# Mini-DSO.net
KiCad netlist of a schematic drawn in Altium Designer
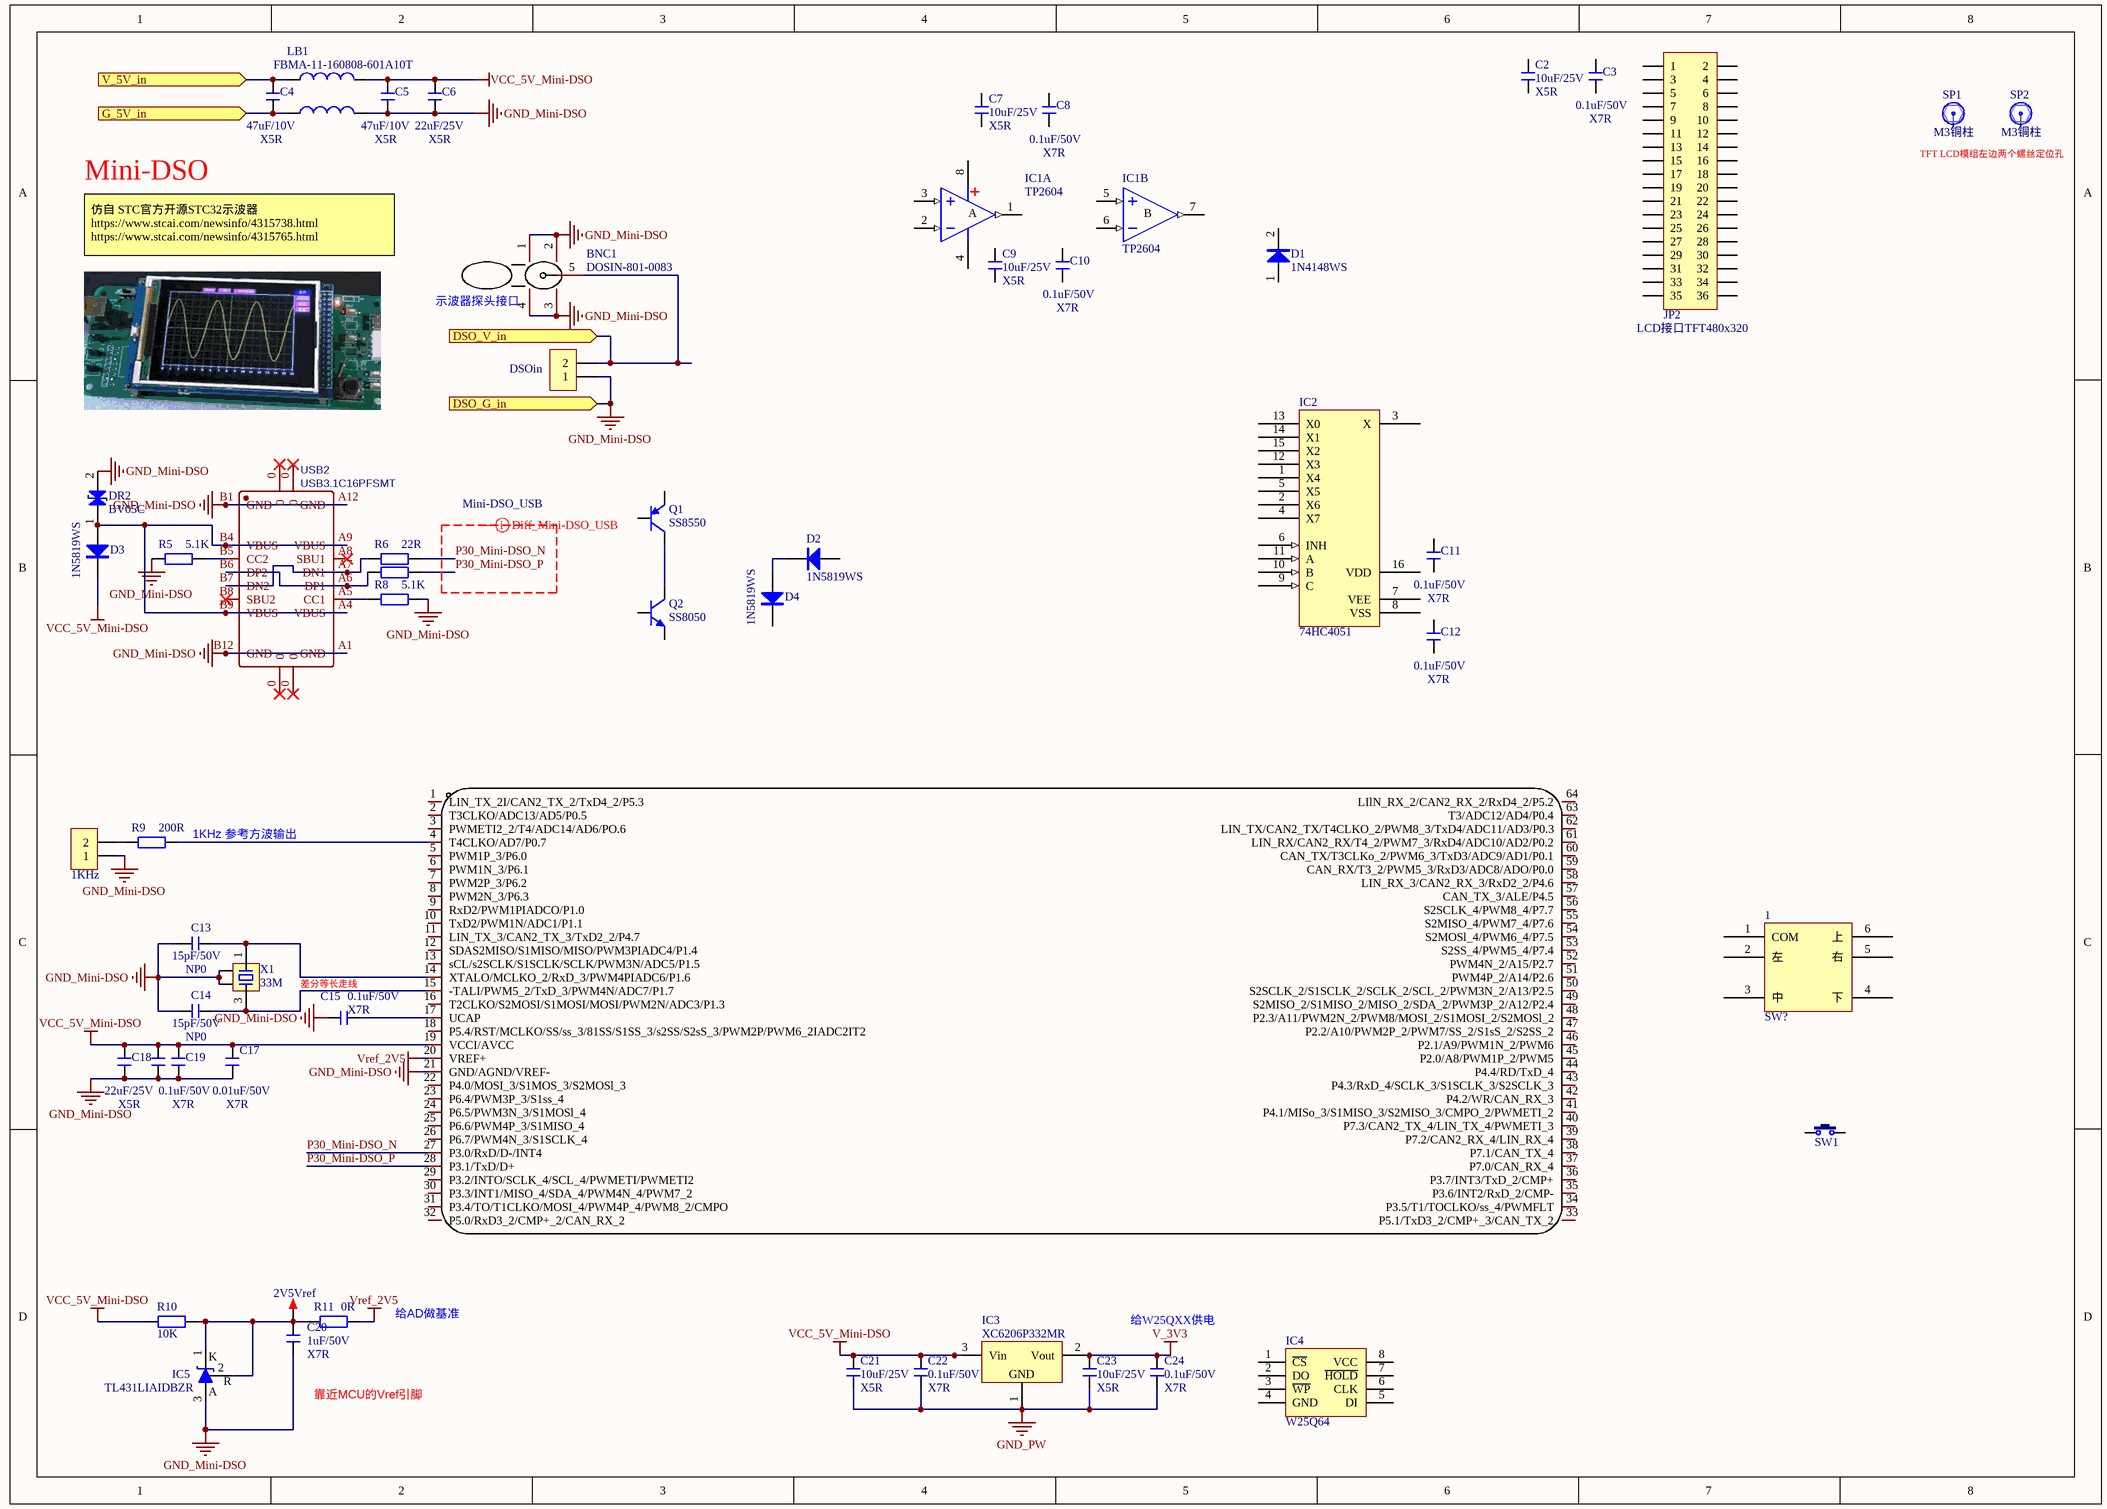
[diagram p0: Mini-DSO.SchDoc]

(export (version "E")
  (design (tool "Eeschema 10.0.6"))
  (components
    (comp (ref "1")
      (value "SW?")
      (footprint "TSW 10x10x9-5Key-LS")
      (description "五向按键")
      (libsource (lib "IC_temp") (part "5Key"))
    )
    (comp (ref "BNC1")
      (value "DOSIN-801-0083")
      (footprint "BNC-TH_DOSIN-801-0083")
      (description "示波器探头插座，DOSIN-801-0083")
      (libsource (lib "IC_temp") (part "BNC插座"))
    )
    (comp (ref "C2")
      (value "10uF/25V")
      (footprint "C 0603_L")
      (description "无极性贴片电容 X5R")
      (fields (field (name "BOM名称") "X5R"))
      (libsource (lib "Foundation_temp") (part "C X5R"))
    )
    (comp (ref "C3")
      (value "0.1uF/50V")
      (footprint "C 0402_L")
      (description "无极性贴片电容 X7R")
      (fields (field (name "BOM名称") "X7R"))
      (libsource (lib "Foundation_temp") (part "C X7R"))
    )
    (comp (ref "C4")
      (value "47uF/10V")
      (footprint "C 1206_L")
      (description "无极性贴片电容 X5R")
      (fields (field (name "BOM名称") "X5R"))
      (libsource (lib "Foundation_temp") (part "C X5R"))
    )
    (comp (ref "C5")
      (value "47uF/10V")
      (footprint "C 1206_L")
      (description "无极性贴片电容 X5R")
      (fields (field (name "BOM名称") "X5R"))
      (libsource (lib "Foundation_temp") (part "C X5R"))
    )
    (comp (ref "C6")
      (value "22uF/25V")
      (footprint "C 0805_L")
      (description "无极性贴片电容 X5R")
      (fields (field (name "BOM名称") "X5R"))
      (libsource (lib "Foundation_temp") (part "C X5R"))
    )
    (comp (ref "C7")
      (value "10uF/25V")
      (footprint "C 0603_L")
      (description "无极性贴片电容 X5R")
      (fields (field (name "BOM名称") "X5R"))
      (libsource (lib "Foundation_temp") (part "C X5R"))
    )
    (comp (ref "C8")
      (value "0.1uF/50V")
      (footprint "C 0402_L")
      (description "无极性贴片电容 X7R")
      (fields (field (name "BOM名称") "X7R"))
      (libsource (lib "Foundation_temp") (part "C X7R"))
    )
    (comp (ref "C9")
      (value "10uF/25V")
      (footprint "C 0603_L")
      (description "无极性贴片电容 X5R")
      (fields (field (name "BOM名称") "X5R"))
      (libsource (lib "Foundation_temp") (part "C X5R"))
    )
    (comp (ref "C10")
      (value "0.1uF/50V")
      (footprint "C 0402_L")
      (description "无极性贴片电容 X7R")
      (fields (field (name "BOM名称") "X7R"))
      (libsource (lib "Foundation_temp") (part "C X7R"))
    )
    (comp (ref "C11")
      (value "0.1uF/50V")
      (footprint "C 0402_L")
      (description "无极性贴片电容 X7R")
      (fields (field (name "BOM名称") "X7R"))
      (libsource (lib "Foundation_temp") (part "C X7R"))
    )
    (comp (ref "C12")
      (value "0.1uF/50V")
      (footprint "C 0402_L")
      (description "无极性贴片电容 X7R")
      (fields (field (name "BOM名称") "X7R"))
      (libsource (lib "Foundation_temp") (part "C X7R"))
    )
    (comp (ref "C13")
      (value "15pF/50V")
      (footprint "C 0402_L")
      (description "无极性贴片电容 NP0")
      (fields (field (name "BOM名称") "NP0"))
      (libsource (lib "Foundation_temp") (part "C NP0"))
    )
    (comp (ref "C14")
      (value "15pF/50V")
      (footprint "C 0402_L")
      (description "无极性贴片电容 NP0")
      (fields (field (name "BOM名称") "NP0"))
      (libsource (lib "Foundation_temp") (part "C NP0"))
    )
    (comp (ref "C15")
      (value "0.1uF/50V")
      (footprint "C 0402_L")
      (description "无极性贴片电容 X7R")
      (fields (field (name "BOM名称") "X7R"))
      (libsource (lib "Foundation_temp") (part "C X7R"))
    )
    (comp (ref "C16")
      (value "0.1uF/50V")
      (footprint "C 0402_L")
      (description "无极性贴片电容 X7R")
      (libsource (lib "Foundation_temp") (part "C X7R"))
    )
    (comp (ref "C17")
      (value "0.01uF/50V")
      (footprint "C 0402_L")
      (description "无极性贴片电容 X7R")
      (fields (field (name "BOM名称") "X7R"))
      (libsource (lib "Foundation_temp") (part "C X7R"))
    )
    (comp (ref "C18")
      (value "22uF/25V")
      (footprint "C 0805_L")
      (description "无极性贴片电容 X5R")
      (fields (field (name "BOM名称") "X5R"))
      (libsource (lib "Foundation_temp") (part "C X5R"))
    )
    (comp (ref "C19")
      (value "0.1uF/50V")
      (footprint "C 0402_L")
      (description "无极性贴片电容 X7R")
      (fields (field (name "BOM名称") "X7R"))
      (libsource (lib "Foundation_temp") (part "C X7R"))
    )
    (comp (ref "C20")
      (value "1uF/50V")
      (footprint "C 0603_L")
      (description "无极性贴片电容 X7R")
      (fields (field (name "BOM名称") "X7R"))
      (libsource (lib "Foundation_temp") (part "C X7R"))
    )
    (comp (ref "C21")
      (value "10uF/25V")
      (footprint "C 0603_L")
      (description "无极性贴片电容 X5R")
      (fields (field (name "BOM名称") "X5R"))
      (libsource (lib "Foundation_temp") (part "C X5R"))
    )
    (comp (ref "C22")
      (value "0.1uF/50V")
      (footprint "C 0402_L")
      (description "无极性贴片电容 X7R")
      (fields (field (name "BOM名称") "X7R"))
      (libsource (lib "Foundation_temp") (part "C X7R"))
    )
    (comp (ref "C23")
      (value "10uF/25V")
      (footprint "C 0603_L")
      (description "无极性贴片电容 X5R")
      (fields (field (name "BOM名称") "X5R"))
      (libsource (lib "Foundation_temp") (part "C X5R"))
    )
    (comp (ref "C24")
      (value "0.1uF/50V")
      (footprint "C 0402_L")
      (description "无极性贴片电容 X7R")
      (fields (field (name "BOM名称") "X7R"))
      (libsource (lib "Foundation_temp") (part "C X7R"))
    )
    (comp (ref "D1")
      (value "1N4148WS")
      (footprint "SOD-323")
      (description "高速开关二极管")
      (fields (field (name "版权归属") "源创客"))
      (libsource (lib "8.1   - 二极管-整流桥") (part "1N4148"))
    )
    (comp (ref "D2")
      (value "1N5819WS")
      (footprint "SOD-323")
      (description "肖特基二极管")
      (fields (field (name "版权归属") "源创客"))
      (libsource (lib "8.1   - 二极管-整流桥") (part "1N5819"))
    )
    (comp (ref "D3")
      (value "1N5819WS")
      (footprint "SOD-323")
      (description "肖特基二极管")
      (fields (field (name "版权归属") "源创客"))
      (libsource (lib "8.1   - 二极管-整流桥") (part "1N5819"))
    )
    (comp (ref "D4")
      (value "1N5819WS")
      (footprint "SOD-323")
      (description "肖特基二极管")
      (fields (field (name "版权归属") "源创客"))
      (libsource (lib "8.1   - 二极管-整流桥") (part "1N5819"))
    )
    (comp (ref "DR2")
      (value "BV05C")
      (footprint "SOD-323")
      (description "瞬态电压抑制二极管")
      (fields (field (name "版权归属") "源创客"))
      (libsource (lib "8.1   - 二极管-整流桥") (part "DR"))
    )
    (comp (ref "IC1")
      (value "TP2604")
      (footprint "SOP8_N")
      (description "双路运放")
      (fields (field (name "版权归属") "源创客"))
      (libsource (lib "1.5   - 运放-功放") (part "LM358"))
    )
    (comp (ref "IC2")
      (value "74HC4051")
      (footprint "SOP16_N")
      (description "八选一")
      (libsource (lib "IC_temp") (part "CD4051"))
    )
    (comp (ref "IC3")
      (value "XC6206P332MR")
      (footprint "SOT23-3N")
      (description "低压差线性稳压芯片")
      (fields (field (name "版权归属") "源创客"))
      (libsource (lib "1.3   - 电源类芯片") (part "XC6206P332MR"))
    )
    (comp (ref "IC4")
      (value "W25Q64")
      (footprint "SOP8W_N")
      (description "外置Flash")
      (fields (field (name "版权归属") "源创客"))
      (libsource (lib "1.1   - IC芯片") (part "W25Qxx"))
    )
    (comp (ref "IC5")
      (value "TL431LIAIDBZR")
      (footprint "SOT23-3N")
      (description "可调基准稳压芯片")
      (fields (field (name "版权归属") "源创客"))
      (libsource (lib "1.3   - 电源类芯片") (part "TL431_SMD"))
    )
    (comp (ref "JP1")
      (value "DSOin")
      (footprint "HDR2.54-WS-2P")
      (description "2P接插件")
      (fields (field (name "版权归属") "源创客"))
      (libsource (lib "4.6   - 接插件-脚距2.54") (part "Header 2"))
    )
    (comp (ref "JP2")
      (value "LCD接口TFT480x320")
      (footprint "HDR2.54-LI-2x18P")
      (description "18*2P接插件")
      (fields (field (name "版权归属") "源创客"))
      (libsource (lib "4.6   - 接插件-脚距2.54") (part "Header 18X2"))
    )
    (comp (ref "JP3")
      (value "1KHz")
      (footprint "HDR2.54-WS-2P")
      (description "2P接插件")
      (fields (field (name "版权归属") "源创客"))
      (libsource (lib "4.6   - 接插件-脚距2.54") (part "Header 2"))
    )
    (comp (ref "LB1")
      (value "FBMA-11-160808-601A10T")
      (footprint "FB 0603_L")
      (description "磁珠 600R@100MHz")
      (fields (field (name "版权归属") "源创客"))
      (libsource (lib "3.1   - 电阻-电容-电感") (part "LB"))
    )
    (comp (ref "LB2")
      (value "FBMA-11-160808-601A10T")
      (footprint "FB 0603_L")
      (description "磁珠 600R@100MHz")
      (fields (field (name "版权归属") "源创客"))
      (libsource (lib "3.1   - 电阻-电容-电感") (part "LB"))
    )
    (comp (ref "Q1")
      (value "SS8550")
      (footprint "SOT23-3N")
      (description "高频放大-PNP型")
      (fields (field (name "版权归属") "源创客"))
      (libsource (lib "6.2   - 三极管") (part "8550-SMD"))
    )
    (comp (ref "Q2")
      (value "SS8050")
      (footprint "SOT23-3N")
      (description "高频放大-NPN型")
      (fields (field (name "版权归属") "源创客"))
      (libsource (lib "6.2   - 三极管") (part "8050-SMD"))
    )
    (comp (ref "R5")
      (value "5.1K")
      (footprint "R 0402_L")
      (description "贴片电阻 E-96 1%")
      (libsource (lib "Foundation_temp") (part "R"))
    )
    (comp (ref "R6")
      (value "22R")
      (footprint "R 0402_L")
      (description "贴片电阻 E-96 1%")
      (libsource (lib "Foundation_temp") (part "R"))
    )
    (comp (ref "R7")
      (value "22R")
      (footprint "R 0402_L")
      (description "贴片电阻 E-96 1%")
      (libsource (lib "Foundation_temp") (part "R"))
    )
    (comp (ref "R8")
      (value "5.1K")
      (footprint "R 0402_L")
      (description "贴片电阻 E-96 1%")
      (libsource (lib "Foundation_temp") (part "R"))
    )
    (comp (ref "R9")
      (value "200R")
      (footprint "R 0402_L")
      (description "贴片电阻 E-96 1%")
      (libsource (lib "Foundation_temp") (part "R"))
    )
    (comp (ref "R10")
      (value "10K")
      (footprint "R 0402_L")
      (description "贴片电阻 E-96 1%")
      (libsource (lib "Foundation_temp") (part "R"))
    )
    (comp (ref "R11")
      (value "0R")
      (footprint "R 0402_L")
      (description "贴片电阻 E-96 1%")
      (libsource (lib "Foundation_temp") (part "R"))
    )
    (comp (ref "SP1")
      (value "M3铜柱")
      (footprint "M3x4_L")
      (description "铜柱")
      (fields (field (name "版权归属") "源创客"))
      (libsource (lib "15.1 - 未分类器件") (part "铜柱小焊盘"))
    )
    (comp (ref "SP2")
      (value "M3铜柱")
      (footprint "M3x4_L")
      (description "铜柱")
      (fields (field (name "版权归属") "源创客"))
      (libsource (lib "15.1 - 未分类器件") (part "铜柱小焊盘"))
    )
    (comp (ref "SW1")
      (value "3x6x5")
      (footprint "TSW SMD-3*6*2.5")
      (description "3x6轻触开关")
      (fields (field (name "版权归属") "源创客"))
      (libsource (lib "5.1   - 按键-开关") (part "TSW 3x6"))
    )
    (comp (ref "TP3")
      (value "2V5Vref")
      (footprint "TEST 1")
      (description "测试点")
      (fields (field (name "版权归属") "源创客"))
      (libsource (lib "15.1 - 未分类器件") (part "TEST"))
    )
    (comp (ref "U1")
      (value "STC32G12K128-Beta-LQFP64")
      (footprint "LQFP64 14x14_N")
      (fields (field (name "MANUFACTURER") "STC(宏晶)"))
      (libsource (lib "STC32G12K128-BETA-LQFP64") (part "STC32G12K128-Beta-LQFP64"))
    )
    (comp (ref "USB2")
      (value "USB3.1C16PFSMT")
      (footprint "TYPE-C-USB-17")
      (libsource (lib "type-c-sch") (part "USB3.1C16PFSMT"))
    )
    (comp (ref "X1")
      (value "33M")
      (footprint "OSC 3225-4P")
      (description "4脚无源晶振")
      (fields (field (name "版权归属") "源创客"))
      (libsource (lib "10.1 - 保险丝-晶振") (part "XTAL-4P"))
    )
  )
  (nets
    (net (code "1") (name "/DSO_V_in") (class "Default")
      (node (ref "BNC1") (pin "5") (pinfunction "5_5") (pintype "passive"))
      (node (ref "JP1") (pin "2") (pinfunction "2_2") (pintype "passive"))
    )
    (net (code "2") (name "/G_5V_in") (class "Default")
      (node (ref "C4") (pin "1") (pinfunction "1_1") (pintype "passive"))
      (node (ref "LB2") (pin "1") (pinfunction "1_1") (pintype "passive"))
    )
    (net (code "3") (name "/P30_Mini-DSO_N") (class "Default")
      (node (ref "R6") (pin "1") (pinfunction "1_1") (pintype "passive"))
      (node (ref "U1") (pin "27") (pinfunction "P3.0/RxD/D-/INT4_27") (pintype "passive"))
    )
    (net (code "4") (name "/P30_Mini-DSO_P") (class "Default")
      (node (ref "R7") (pin "1") (pinfunction "1_1") (pintype "passive"))
      (node (ref "U1") (pin "28") (pinfunction "P3.1/TxD/D+_28") (pintype "passive"))
    )
    (net (code "5") (name "/V_5V_in") (class "Default")
      (node (ref "C4") (pin "2") (pinfunction "2_2") (pintype "passive"))
      (node (ref "LB1") (pin "1") (pinfunction "1_1") (pintype "passive"))
    )
    (net (code "6") (name "GND_Mini-DSO") (class "Default")
      (node (ref "BNC1") (pin "1") (pinfunction "1_1") (pintype "passive"))
      (node (ref "BNC1") (pin "2") (pinfunction "2_2") (pintype "passive"))
      (node (ref "BNC1") (pin "3") (pinfunction "3_3") (pintype "passive"))
      (node (ref "BNC1") (pin "4") (pinfunction "4_4") (pintype "passive"))
      (node (ref "C13") (pin "2") (pinfunction "2_2") (pintype "passive"))
      (node (ref "C14") (pin "2") (pinfunction "2_2") (pintype "passive"))
      (node (ref "C15") (pin "2") (pinfunction "2_2") (pintype "passive"))
      (node (ref "C16") (pin "2") (pinfunction "2_2") (pintype "passive"))
      (node (ref "C17") (pin "2") (pinfunction "2_2") (pintype "passive"))
      (node (ref "C18") (pin "1") (pinfunction "1_1") (pintype "passive"))
      (node (ref "C19") (pin "2") (pinfunction "2_2") (pintype "passive"))
      (node (ref "C20") (pin "1") (pinfunction "1_1") (pintype "passive"))
      (node (ref "C5") (pin "1") (pinfunction "1_1") (pintype "passive"))
      (node (ref "C6") (pin "1") (pinfunction "1_1") (pintype "passive"))
      (node (ref "DR2") (pin "2") (pinfunction "K_2") (pintype "passive"))
      (node (ref "IC5") (pin "3") (pinfunction "A_3") (pintype "passive"))
      (node (ref "JP1") (pin "1") (pinfunction "1_1") (pintype "passive"))
      (node (ref "JP3") (pin "1") (pinfunction "1_1") (pintype "passive"))
      (node (ref "LB2") (pin "2") (pinfunction "2_2") (pintype "passive"))
      (node (ref "R5") (pin "2") (pinfunction "2_2") (pintype "passive"))
      (node (ref "R8") (pin "1") (pinfunction "1_1") (pintype "passive"))
      (node (ref "U1") (pin "21") (pinfunction "GND/AGND/VREF-_21") (pintype "passive"))
      (node (ref "USB2") (pin "A1") (pinfunction "GND_A1") (pintype "passive"))
      (node (ref "USB2") (pin "A12") (pinfunction "GND_A12") (pintype "passive"))
      (node (ref "USB2") (pin "B1") (pinfunction "GND_B1") (pintype "passive"))
      (node (ref "USB2") (pin "B12") (pinfunction "GND_B12") (pintype "passive"))
      (node (ref "X1") (pin "2") (pinfunction "2_2") (pintype "passive"))
      (node (ref "X1") (pin "4") (pinfunction "4_4") (pintype "passive"))
    )
    (net (code "7") (name "GND_PW") (class "Default")
      (node (ref "C21") (pin "1") (pinfunction "1_1") (pintype "passive"))
      (node (ref "C22") (pin "2") (pinfunction "2_2") (pintype "passive"))
      (node (ref "C23") (pin "1") (pinfunction "1_1") (pintype "passive"))
      (node (ref "C24") (pin "2") (pinfunction "2_2") (pintype "passive"))
      (node (ref "IC3") (pin "1") (pinfunction "GND_1") (pintype "passive"))
    )
    (net (code "8") (name "Net-(D2-K)") (class "Default")
      (node (ref "D2") (pin "2") (pinfunction "K_2") (pintype "passive"))
      (node (ref "D4") (pin "1") (pinfunction "A_1") (pintype "passive"))
    )
    (net (code "9") (name "Net-(D3-A)") (class "Default")
      (node (ref "D3") (pin "1") (pinfunction "A_1") (pintype "passive"))
      (node (ref "DR2") (pin "1") (pinfunction "A_1") (pintype "passive"))
      (node (ref "USB2") (pin "A4") (pinfunction "VBUS_A4") (pintype "passive"))
      (node (ref "USB2") (pin "A9") (pinfunction "VBUS_A9") (pintype "passive"))
      (node (ref "USB2") (pin "B4") (pinfunction "VBUS_B4") (pintype "passive"))
      (node (ref "USB2") (pin "B9") (pinfunction "VBUS_B9") (pintype "passive"))
    )
    (net (code "10") (name "Net-(IC5-K)") (class "Default")
      (node (ref "C20") (pin "2") (pinfunction "2_2") (pintype "passive"))
      (node (ref "IC5") (pin "1") (pinfunction "K_1") (pintype "passive"))
      (node (ref "IC5") (pin "2") (pinfunction "R_2") (pintype "passive"))
      (node (ref "R10") (pin "1") (pinfunction "1_1") (pintype "passive"))
      (node (ref "R11") (pin "1") (pinfunction "1_1") (pintype "passive"))
      (node (ref "TP3") (pin "1") (pinfunction "1_1") (pintype "passive"))
    )
    (net (code "11") (name "Net-(JP3-Pad2)") (class "Default")
      (node (ref "JP3") (pin "2") (pinfunction "2_2") (pintype "passive"))
      (node (ref "R9") (pin "2") (pinfunction "2_2") (pintype "passive"))
    )
    (net (code "12") (name "Net-(Q1-C)") (class "Default")
      (node (ref "Q1") (pin "3") (pinfunction "C_3") (pintype "passive"))
      (node (ref "Q2") (pin "3") (pinfunction "C_3") (pintype "passive"))
    )
    (net (code "13") (name "Net-(U1--TALI{slash}PWM5_2{slash}TxD_3{slash}PWM4N{slash}ADC7{slash}P1.7)") (class "Default")
      (node (ref "C14") (pin "1") (pinfunction "1_1") (pintype "passive"))
      (node (ref "U1") (pin "15") (pinfunction "-TALI/PWM5_2/TxD_3/PWM4N/ADC7/P1.7_15") (pintype "passive"))
      (node (ref "X1") (pin "3") (pinfunction "3_3") (pintype "passive"))
    )
    (net (code "14") (name "Net-(U1-T4CLKO{slash}AD7{slash}P0.7)") (class "Default")
      (node (ref "R9") (pin "1") (pinfunction "1_1") (pintype "passive"))
      (node (ref "U1") (pin "4") (pinfunction "T4CLKO/AD7/P0.7_4") (pintype "passive"))
    )
    (net (code "15") (name "Net-(U1-UCAP)") (class "Default")
      (node (ref "C15") (pin "1") (pinfunction "1_1") (pintype "passive"))
      (node (ref "U1") (pin "17") (pinfunction "UCAP_17") (pintype "passive"))
    )
    (net (code "16") (name "Net-(U1-XTALO{slash}MCLKO_2{slash}RxD_3{slash}PWM4PIADC6{slash}P1.6)") (class "Default")
      (node (ref "C13") (pin "1") (pinfunction "1_1") (pintype "passive"))
      (node (ref "U1") (pin "14") (pinfunction "XTALO/MCLKO_2/RxD_3/PWM4PIADC6/P1.6_14") (pintype "passive"))
      (node (ref "X1") (pin "1") (pinfunction "1_1") (pintype "passive"))
    )
    (net (code "17") (name "Net-(USB2-CC1)") (class "Default")
      (node (ref "R8") (pin "2") (pinfunction "2_2") (pintype "passive"))
      (node (ref "USB2") (pin "A5") (pinfunction "CC1_A5") (pintype "passive"))
    )
    (net (code "18") (name "Net-(USB2-CC2)") (class "Default")
      (node (ref "R5") (pin "1") (pinfunction "1_1") (pintype "passive"))
      (node (ref "USB2") (pin "B5") (pinfunction "CC2_B5") (pintype "passive"))
    )
    (net (code "19") (name "Net-(USB2-DN1)") (class "Default")
      (node (ref "R6") (pin "2") (pinfunction "2_2") (pintype "passive"))
      (node (ref "USB2") (pin "A7") (pinfunction "DN1_A7") (pintype "passive"))
      (node (ref "USB2") (pin "B7") (pinfunction "DN2_B7") (pintype "passive"))
    )
    (net (code "20") (name "Net-(USB2-DP1)") (class "Default")
      (node (ref "R7") (pin "2") (pinfunction "2_2") (pintype "passive"))
      (node (ref "USB2") (pin "A6") (pinfunction "DP1_A6") (pintype "passive"))
      (node (ref "USB2") (pin "B6") (pinfunction "DP2_B6") (pintype "passive"))
    )
    (net (code "21") (name "VCC_5V_Mini-DSO") (class "Default")
      (node (ref "C16") (pin "1") (pinfunction "1_1") (pintype "passive"))
      (node (ref "C17") (pin "1") (pinfunction "1_1") (pintype "passive"))
      (node (ref "C18") (pin "2") (pinfunction "2_2") (pintype "passive"))
      (node (ref "C19") (pin "1") (pinfunction "1_1") (pintype "passive"))
      (node (ref "C21") (pin "2") (pinfunction "2_2") (pintype "passive"))
      (node (ref "C22") (pin "1") (pinfunction "1_1") (pintype "passive"))
      (node (ref "C5") (pin "2") (pinfunction "2_2") (pintype "passive"))
      (node (ref "C6") (pin "2") (pinfunction "2_2") (pintype "passive"))
      (node (ref "D3") (pin "2") (pinfunction "K_2") (pintype "passive"))
      (node (ref "IC3") (pin "3") (pinfunction "Vin_3") (pintype "passive"))
      (node (ref "LB1") (pin "2") (pinfunction "2_2") (pintype "passive"))
      (node (ref "R10") (pin "2") (pinfunction "2_2") (pintype "passive"))
      (node (ref "U1") (pin "19") (pinfunction "VCCI/AVCC_19") (pintype "passive"))
    )
    (net (code "22") (name "V_3V3") (class "Default")
      (node (ref "C23") (pin "2") (pinfunction "2_2") (pintype "passive"))
      (node (ref "C24") (pin "1") (pinfunction "1_1") (pintype "passive"))
      (node (ref "IC3") (pin "2") (pinfunction "Vout_2") (pintype "passive"))
    )
    (net (code "23") (name "Vref_2V5") (class "Default")
      (node (ref "R11") (pin "2") (pinfunction "2_2") (pintype "passive"))
      (node (ref "U1") (pin "20") (pinfunction "VREF+_20") (pintype "passive"))
    )
    (net (code "24") (name "unconnected-(1-COM-Pad1)") (class "Default")
      (node (ref "1") (pin "1") (pinfunction "COM_1") (pintype "passive"))
    )
    (net (code "25") (name "unconnected-(1-上-Pad6)") (class "Default")
      (node (ref "1") (pin "6") (pinfunction "上_6") (pintype "passive"))
    )
    (net (code "26") (name "unconnected-(1-下-Pad4)") (class "Default")
      (node (ref "1") (pin "4") (pinfunction "下_4") (pintype "passive"))
    )
    (net (code "27") (name "unconnected-(1-中-Pad3)") (class "Default")
      (node (ref "1") (pin "3") (pinfunction "中_3") (pintype "passive"))
    )
    (net (code "28") (name "unconnected-(1-右-Pad5)") (class "Default")
      (node (ref "1") (pin "5") (pinfunction "右_5") (pintype "passive"))
    )
    (net (code "29") (name "unconnected-(1-左-Pad2)") (class "Default")
      (node (ref "1") (pin "2") (pinfunction "左_2") (pintype "passive"))
    )
    (net (code "30") (name "unconnected-(C2-Pad1)") (class "Default")
      (node (ref "C2") (pin "1") (pinfunction "1_1") (pintype "passive"))
    )
    (net (code "31") (name "unconnected-(C2-Pad2)") (class "Default")
      (node (ref "C2") (pin "2") (pinfunction "2_2") (pintype "passive"))
    )
    (net (code "32") (name "unconnected-(C3-Pad1)") (class "Default")
      (node (ref "C3") (pin "1") (pinfunction "1_1") (pintype "passive"))
    )
    (net (code "33") (name "unconnected-(C3-Pad2)") (class "Default")
      (node (ref "C3") (pin "2") (pinfunction "2_2") (pintype "passive"))
    )
    (net (code "34") (name "unconnected-(C7-Pad1)") (class "Default")
      (node (ref "C7") (pin "1") (pinfunction "1_1") (pintype "passive"))
    )
    (net (code "35") (name "unconnected-(C7-Pad2)") (class "Default")
      (node (ref "C7") (pin "2") (pinfunction "2_2") (pintype "passive"))
    )
    (net (code "36") (name "unconnected-(C8-Pad1)") (class "Default")
      (node (ref "C8") (pin "1") (pinfunction "1_1") (pintype "passive"))
    )
    (net (code "37") (name "unconnected-(C8-Pad2)") (class "Default")
      (node (ref "C8") (pin "2") (pinfunction "2_2") (pintype "passive"))
    )
    (net (code "38") (name "unconnected-(C9-Pad1)") (class "Default")
      (node (ref "C9") (pin "1") (pinfunction "1_1") (pintype "passive"))
    )
    (net (code "39") (name "unconnected-(C9-Pad2)") (class "Default")
      (node (ref "C9") (pin "2") (pinfunction "2_2") (pintype "passive"))
    )
    (net (code "40") (name "unconnected-(C10-Pad1)") (class "Default")
      (node (ref "C10") (pin "1") (pinfunction "1_1") (pintype "passive"))
    )
    (net (code "41") (name "unconnected-(C10-Pad2)") (class "Default")
      (node (ref "C10") (pin "2") (pinfunction "2_2") (pintype "passive"))
    )
    (net (code "42") (name "unconnected-(C11-Pad1)") (class "Default")
      (node (ref "C11") (pin "1") (pinfunction "1_1") (pintype "passive"))
    )
    (net (code "43") (name "unconnected-(C11-Pad2)") (class "Default")
      (node (ref "C11") (pin "2") (pinfunction "2_2") (pintype "passive"))
    )
    (net (code "44") (name "unconnected-(C12-Pad1)") (class "Default")
      (node (ref "C12") (pin "1") (pinfunction "1_1") (pintype "passive"))
    )
    (net (code "45") (name "unconnected-(C12-Pad2)") (class "Default")
      (node (ref "C12") (pin "2") (pinfunction "2_2") (pintype "passive"))
    )
    (net (code "46") (name "unconnected-(D1-A-Pad1)") (class "Default")
      (node (ref "D1") (pin "1") (pinfunction "A_1") (pintype "passive"))
    )
    (net (code "47") (name "unconnected-(D1-K-Pad2)") (class "Default")
      (node (ref "D1") (pin "2") (pinfunction "K_2") (pintype "passive"))
    )
    (net (code "48") (name "unconnected-(D2-A-Pad1)") (class "Default")
      (node (ref "D2") (pin "1") (pinfunction "A_1") (pintype "passive"))
    )
    (net (code "49") (name "unconnected-(D4-K-Pad2)") (class "Default")
      (node (ref "D4") (pin "2") (pinfunction "K_2") (pintype "passive"))
    )
    (net (code "50") (name "unconnected-(IC1A-IN+-Pad3)") (class "Default")
      (node (ref "IC1") (pin "3") (pinfunction "IN+_3") (pintype "input"))
    )
    (net (code "51") (name "unconnected-(IC1A-IN--Pad2)") (class "Default")
      (node (ref "IC1") (pin "2") (pinfunction "IN-_2") (pintype "input"))
    )
    (net (code "52") (name "unconnected-(IC1A-OUT-Pad1)") (class "Default")
      (node (ref "IC1") (pin "1") (pinfunction "OUT_1") (pintype "output"))
    )
    (net (code "53") (name "unconnected-(IC1A-V+-Pad8)") (class "Default")
      (node (ref "IC1") (pin "8") (pinfunction "V+_8") (pintype "power_in"))
    )
    (net (code "54") (name "unconnected-(IC1A-V--Pad4)") (class "Default")
      (node (ref "IC1") (pin "4") (pinfunction "V-_4") (pintype "power_in"))
    )
    (net (code "55") (name "unconnected-(IC1B-IN+-Pad5)") (class "Default")
      (node (ref "IC1") (pin "5") (pinfunction "IN+_5") (pintype "input"))
    )
    (net (code "56") (name "unconnected-(IC1B-IN--Pad6)") (class "Default")
      (node (ref "IC1") (pin "6") (pinfunction "IN-_6") (pintype "input"))
    )
    (net (code "57") (name "unconnected-(IC1B-OUT-Pad7)") (class "Default")
      (node (ref "IC1") (pin "7") (pinfunction "OUT_7") (pintype "output"))
    )
    (net (code "58") (name "unconnected-(IC2-A-Pad11)") (class "Default")
      (node (ref "IC2") (pin "11") (pinfunction "A_11") (pintype "input"))
    )
    (net (code "59") (name "unconnected-(IC2-B-Pad10)") (class "Default")
      (node (ref "IC2") (pin "10") (pinfunction "B_10") (pintype "input"))
    )
    (net (code "60") (name "unconnected-(IC2-C-Pad9)") (class "Default")
      (node (ref "IC2") (pin "9") (pinfunction "C_9") (pintype "input"))
    )
    (net (code "61") (name "unconnected-(IC2-INH-Pad6)") (class "Default")
      (node (ref "IC2") (pin "6") (pinfunction "INH_6") (pintype "input"))
    )
    (net (code "62") (name "unconnected-(IC2-VDD-Pad16)") (class "Default")
      (node (ref "IC2") (pin "16") (pinfunction "VDD_16") (pintype "power_in"))
    )
    (net (code "63") (name "unconnected-(IC2-VEE-Pad7)") (class "Default")
      (node (ref "IC2") (pin "7") (pinfunction "VEE_7") (pintype "passive"))
    )
    (net (code "64") (name "unconnected-(IC2-VSS-Pad8)") (class "Default")
      (node (ref "IC2") (pin "8") (pinfunction "VSS_8") (pintype "power_in"))
    )
    (net (code "65") (name "unconnected-(IC2-X-Pad3)") (class "Default")
      (node (ref "IC2") (pin "3") (pinfunction "X_3") (pintype "passive"))
    )
    (net (code "66") (name "unconnected-(IC2-X0-Pad13)") (class "Default")
      (node (ref "IC2") (pin "13") (pinfunction "X0_13") (pintype "passive"))
    )
    (net (code "67") (name "unconnected-(IC2-X1-Pad14)") (class "Default")
      (node (ref "IC2") (pin "14") (pinfunction "X1_14") (pintype "passive"))
    )
    (net (code "68") (name "unconnected-(IC2-X2-Pad15)") (class "Default")
      (node (ref "IC2") (pin "15") (pinfunction "X2_15") (pintype "passive"))
    )
    (net (code "69") (name "unconnected-(IC2-X3-Pad12)") (class "Default")
      (node (ref "IC2") (pin "12") (pinfunction "X3_12") (pintype "passive"))
    )
    (net (code "70") (name "unconnected-(IC2-X4-Pad1)") (class "Default")
      (node (ref "IC2") (pin "1") (pinfunction "X4_1") (pintype "passive"))
    )
    (net (code "71") (name "unconnected-(IC2-X5-Pad5)") (class "Default")
      (node (ref "IC2") (pin "5") (pinfunction "X5_5") (pintype "passive"))
    )
    (net (code "72") (name "unconnected-(IC2-X6-Pad2)") (class "Default")
      (node (ref "IC2") (pin "2") (pinfunction "X6_2") (pintype "passive"))
    )
    (net (code "73") (name "unconnected-(IC2-X7-Pad4)") (class "Default")
      (node (ref "IC2") (pin "4") (pinfunction "X7_4") (pintype "passive"))
    )
    (net (code "74") (name "unconnected-(IC4-CLK-Pad6)") (class "Default")
      (node (ref "IC4") (pin "6") (pinfunction "CLK_6") (pintype "passive"))
    )
    (net (code "75") (name "unconnected-(IC4-DI-Pad5)") (class "Default")
      (node (ref "IC4") (pin "5") (pinfunction "DI_5") (pintype "passive"))
    )
    (net (code "76") (name "unconnected-(IC4-DO-Pad2)") (class "Default")
      (node (ref "IC4") (pin "2") (pinfunction "DO_2") (pintype "passive"))
    )
    (net (code "77") (name "unconnected-(IC4-GND-Pad4)") (class "Default")
      (node (ref "IC4") (pin "4") (pinfunction "GND_4") (pintype "passive"))
    )
    (net (code "78") (name "unconnected-(IC4-VCC-Pad8)") (class "Default")
      (node (ref "IC4") (pin "8") (pinfunction "VCC_8") (pintype "passive"))
    )
    (net (code "79") (name "unconnected-(IC4-~{CS}-Pad1)") (class "Default")
      (node (ref "IC4") (pin "1") (pinfunction "~{CS}_1") (pintype "passive"))
    )
    (net (code "80") (name "unconnected-(IC4-~{HOLD}-Pad7)") (class "Default")
      (node (ref "IC4") (pin "7") (pinfunction "~{HOLD}_7") (pintype "passive"))
    )
    (net (code "81") (name "unconnected-(IC4-~{WP}-Pad3)") (class "Default")
      (node (ref "IC4") (pin "3") (pinfunction "~{WP}_3") (pintype "passive"))
    )
    (net (code "82") (name "unconnected-(JP2-Pad1)") (class "Default")
      (node (ref "JP2") (pin "1") (pinfunction "1_1") (pintype "passive"))
    )
    (net (code "83") (name "unconnected-(JP2-Pad2)") (class "Default")
      (node (ref "JP2") (pin "2") (pinfunction "2_2") (pintype "passive"))
    )
    (net (code "84") (name "unconnected-(JP2-Pad3)") (class "Default")
      (node (ref "JP2") (pin "3") (pinfunction "3_3") (pintype "passive"))
    )
    (net (code "85") (name "unconnected-(JP2-Pad4)") (class "Default")
      (node (ref "JP2") (pin "4") (pinfunction "4_4") (pintype "passive"))
    )
    (net (code "86") (name "unconnected-(JP2-Pad5)") (class "Default")
      (node (ref "JP2") (pin "5") (pinfunction "5_5") (pintype "passive"))
    )
    (net (code "87") (name "unconnected-(JP2-Pad6)") (class "Default")
      (node (ref "JP2") (pin "6") (pinfunction "6_6") (pintype "passive"))
    )
    (net (code "88") (name "unconnected-(JP2-Pad7)") (class "Default")
      (node (ref "JP2") (pin "7") (pinfunction "7_7") (pintype "passive"))
    )
    (net (code "89") (name "unconnected-(JP2-Pad8)") (class "Default")
      (node (ref "JP2") (pin "8") (pinfunction "8_8") (pintype "passive"))
    )
    (net (code "90") (name "unconnected-(JP2-Pad9)") (class "Default")
      (node (ref "JP2") (pin "9") (pinfunction "9_9") (pintype "passive"))
    )
    (net (code "91") (name "unconnected-(JP2-Pad10)") (class "Default")
      (node (ref "JP2") (pin "10") (pinfunction "10_10") (pintype "passive"))
    )
    (net (code "92") (name "unconnected-(JP2-Pad11)") (class "Default")
      (node (ref "JP2") (pin "11") (pinfunction "11_11") (pintype "passive"))
    )
    (net (code "93") (name "unconnected-(JP2-Pad12)") (class "Default")
      (node (ref "JP2") (pin "12") (pinfunction "12_12") (pintype "passive"))
    )
    (net (code "94") (name "unconnected-(JP2-Pad13)") (class "Default")
      (node (ref "JP2") (pin "13") (pinfunction "13_13") (pintype "passive"))
    )
    (net (code "95") (name "unconnected-(JP2-Pad14)") (class "Default")
      (node (ref "JP2") (pin "14") (pinfunction "14_14") (pintype "passive"))
    )
    (net (code "96") (name "unconnected-(JP2-Pad15)") (class "Default")
      (node (ref "JP2") (pin "15") (pinfunction "15_15") (pintype "passive"))
    )
    (net (code "97") (name "unconnected-(JP2-Pad16)") (class "Default")
      (node (ref "JP2") (pin "16") (pinfunction "16_16") (pintype "passive"))
    )
    (net (code "98") (name "unconnected-(JP2-Pad17)") (class "Default")
      (node (ref "JP2") (pin "17") (pinfunction "17_17") (pintype "passive"))
    )
    (net (code "99") (name "unconnected-(JP2-Pad18)") (class "Default")
      (node (ref "JP2") (pin "18") (pinfunction "18_18") (pintype "passive"))
    )
    (net (code "100") (name "unconnected-(JP2-Pad19)") (class "Default")
      (node (ref "JP2") (pin "19") (pinfunction "19_19") (pintype "passive"))
    )
    (net (code "101") (name "unconnected-(JP2-Pad20)") (class "Default")
      (node (ref "JP2") (pin "20") (pinfunction "20_20") (pintype "passive"))
    )
    (net (code "102") (name "unconnected-(JP2-Pad21)") (class "Default")
      (node (ref "JP2") (pin "21") (pinfunction "21_21") (pintype "passive"))
    )
    (net (code "103") (name "unconnected-(JP2-Pad22)") (class "Default")
      (node (ref "JP2") (pin "22") (pinfunction "22_22") (pintype "passive"))
    )
    (net (code "104") (name "unconnected-(JP2-Pad23)") (class "Default")
      (node (ref "JP2") (pin "23") (pinfunction "23_23") (pintype "passive"))
    )
    (net (code "105") (name "unconnected-(JP2-Pad24)") (class "Default")
      (node (ref "JP2") (pin "24") (pinfunction "24_24") (pintype "passive"))
    )
    (net (code "106") (name "unconnected-(JP2-Pad25)") (class "Default")
      (node (ref "JP2") (pin "25") (pinfunction "25_25") (pintype "passive"))
    )
    (net (code "107") (name "unconnected-(JP2-Pad26)") (class "Default")
      (node (ref "JP2") (pin "26") (pinfunction "26_26") (pintype "passive"))
    )
    (net (code "108") (name "unconnected-(JP2-Pad27)") (class "Default")
      (node (ref "JP2") (pin "27") (pinfunction "27_27") (pintype "passive"))
    )
    (net (code "109") (name "unconnected-(JP2-Pad28)") (class "Default")
      (node (ref "JP2") (pin "28") (pinfunction "28_28") (pintype "passive"))
    )
    (net (code "110") (name "unconnected-(JP2-Pad29)") (class "Default")
      (node (ref "JP2") (pin "29") (pinfunction "29_29") (pintype "passive"))
    )
    (net (code "111") (name "unconnected-(JP2-Pad30)") (class "Default")
      (node (ref "JP2") (pin "30") (pinfunction "30_30") (pintype "passive"))
    )
    (net (code "112") (name "unconnected-(JP2-Pad31)") (class "Default")
      (node (ref "JP2") (pin "31") (pinfunction "31_31") (pintype "passive"))
    )
    (net (code "113") (name "unconnected-(JP2-Pad32)") (class "Default")
      (node (ref "JP2") (pin "32") (pinfunction "32_32") (pintype "passive"))
    )
    (net (code "114") (name "unconnected-(JP2-Pad33)") (class "Default")
      (node (ref "JP2") (pin "33") (pinfunction "33_33") (pintype "passive"))
    )
    (net (code "115") (name "unconnected-(JP2-Pad34)") (class "Default")
      (node (ref "JP2") (pin "34") (pinfunction "34_34") (pintype "passive"))
    )
    (net (code "116") (name "unconnected-(JP2-Pad35)") (class "Default")
      (node (ref "JP2") (pin "35") (pinfunction "35_35") (pintype "passive"))
    )
    (net (code "117") (name "unconnected-(JP2-Pad36)") (class "Default")
      (node (ref "JP2") (pin "36") (pinfunction "36_36") (pintype "passive"))
    )
    (net (code "118") (name "unconnected-(Q1-B-Pad1)") (class "Default")
      (node (ref "Q1") (pin "1") (pinfunction "B_1") (pintype "passive"))
    )
    (net (code "119") (name "unconnected-(Q1-E-Pad2)") (class "Default")
      (node (ref "Q1") (pin "2") (pinfunction "E_2") (pintype "passive"))
    )
    (net (code "120") (name "unconnected-(Q2-B-Pad1)") (class "Default")
      (node (ref "Q2") (pin "1") (pinfunction "B_1") (pintype "passive"))
    )
    (net (code "121") (name "unconnected-(Q2-E-Pad2)") (class "Default")
      (node (ref "Q2") (pin "2") (pinfunction "E_2") (pintype "passive"))
    )
    (net (code "122") (name "unconnected-(SP1-Pad1)") (class "Default")
      (node (ref "SP1") (pin "1") (pinfunction "1_1") (pintype "passive"))
    )
    (net (code "123") (name "unconnected-(SP2-Pad1)") (class "Default")
      (node (ref "SP2") (pin "1") (pinfunction "1_1") (pintype "passive"))
    )
    (net (code "124") (name "unconnected-(SW1-Pad1)") (class "Default")
      (node (ref "SW1") (pin "1") (pinfunction "1_1") (pintype "passive"))
    )
    (net (code "125") (name "unconnected-(SW1-Pad2)") (class "Default")
      (node (ref "SW1") (pin "2") (pinfunction "2_2") (pintype "passive"))
    )
    (net (code "126") (name "unconnected-(U1-CAN_RX{slash}T3_2{slash}PWM5_3{slash}RxD3{slash}ADC8{slash}ADO{slash}P0.0-Pad59)") (class "Default")
      (node (ref "U1") (pin "59") (pinfunction "CAN_RX/T3_2/PWM5_3/RxD3/ADC8/ADO/P0.0_59") (pintype "passive"))
    )
    (net (code "127") (name "unconnected-(U1-CAN_TX_3{slash}ALE{slash}P4.5-Pad57)") (class "Default")
      (node (ref "U1") (pin "57") (pinfunction "CAN_TX_3/ALE/P4.5_57") (pintype "passive"))
    )
    (net (code "128") (name "unconnected-(U1-CAN_TX{slash}T3CLKo_2{slash}PWM6_3{slash}TxD3{slash}ADC9{slash}AD1{slash}P0.1-Pad60)") (class "Default")
      (node (ref "U1") (pin "60") (pinfunction "CAN_TX/T3CLKo_2/PWM6_3/TxD3/ADC9/AD1/P0.1_60") (pintype "passive"))
    )
    (net (code "129") (name "unconnected-(U1-LIN_RX_3{slash}CAN2_RX_3{slash}RxD2_2{slash}P4.6-Pad58)") (class "Default")
      (node (ref "U1") (pin "58") (pinfunction "LIN_RX_3/CAN2_RX_3/RxD2_2/P4.6_58") (pintype "passive"))
    )
    (net (code "130") (name "unconnected-(U1-LIN_RX{slash}CAN2_RX{slash}T4_2{slash}PWM7_3{slash}RxD4{slash}ADC10{slash}AD2{slash}P0.2-Pad61)") (class "Default")
      (node (ref "U1") (pin "61") (pinfunction "LIN_RX/CAN2_RX/T4_2/PWM7_3/RxD4/ADC10/AD2/P0.2_61") (pintype "passive"))
    )
    (net (code "131") (name "unconnected-(U1-LIN_TX_2I{slash}CAN2_TX_2{slash}TxD4_2{slash}P5.3-Pad1)") (class "Default")
      (node (ref "U1") (pin "1") (pinfunction "LIN_TX_2I/CAN2_TX_2/TxD4_2/P5.3_1") (pintype "passive"))
    )
    (net (code "132") (name "unconnected-(U1-LIN_TX_3{slash}CAN2_TX_3{slash}TxD2_2{slash}P4.7-Pad11)") (class "Default")
      (node (ref "U1") (pin "11") (pinfunction "LIN_TX_3/CAN2_TX_3/TxD2_2/P4.7_11") (pintype "passive"))
    )
    (net (code "133") (name "unconnected-(U1-LIN_TX{slash}CAN2_TX{slash}T4CLKO_2{slash}PWM8_3{slash}TxD4{slash}ADC11{slash}AD3{slash}P0.3-Pad62)") (class "Default")
      (node (ref "U1") (pin "62") (pinfunction "LIN_TX/CAN2_TX/T4CLKO_2/PWM8_3/TxD4/ADC11/AD3/P0.3_62") (pintype "passive"))
    )
    (net (code "134") (name "unconnected-(U1-LIlN_RX_2{slash}CAN2_RX_2{slash}RxD4_2{slash}P5.2-Pad64)") (class "Default")
      (node (ref "U1") (pin "64") (pinfunction "LIlN_RX_2/CAN2_RX_2/RxD4_2/P5.2_64") (pintype "passive"))
    )
    (net (code "135") (name "unconnected-(U1-P2.0{slash}A8{slash}PWM1P_2{slash}PWM5-Pad45)") (class "Default")
      (node (ref "U1") (pin "45") (pinfunction "P2.0/A8/PWM1P_2/PWM5_45") (pintype "passive"))
    )
    (net (code "136") (name "unconnected-(U1-P2.1{slash}A9{slash}PWM1N_2{slash}PWM6-Pad46)") (class "Default")
      (node (ref "U1") (pin "46") (pinfunction "P2.1/A9/PWM1N_2/PWM6_46") (pintype "passive"))
    )
    (net (code "137") (name "unconnected-(U1-P2.2{slash}A10{slash}PWM2P_2{slash}PWM7{slash}SS_2{slash}S1sS_2{slash}S2SS_2-Pad47)") (class "Default")
      (node (ref "U1") (pin "47") (pinfunction "P2.2/A10/PWM2P_2/PWM7/SS_2/S1sS_2/S2SS_2_47") (pintype "passive"))
    )
    (net (code "138") (name "unconnected-(U1-P2.3{slash}A11{slash}PWM2N_2{slash}PWM8{slash}MOSI_2{slash}S1MOSI_2{slash}S2MOSl_2-Pad48)") (class "Default")
      (node (ref "U1") (pin "48") (pinfunction "P2.3/A11/PWM2N_2/PWM8/MOSI_2/S1MOSI_2/S2MOSl_2_48") (pintype "passive"))
    )
    (net (code "139") (name "unconnected-(U1-P3.2{slash}INTO{slash}SCLK_4{slash}SCL_4{slash}PWMETI{slash}PWMETI2-Pad29)") (class "Default")
      (node (ref "U1") (pin "29") (pinfunction "P3.2/INTO/SCLK_4/SCL_4/PWMETI/PWMETI2_29") (pintype "passive"))
    )
    (net (code "140") (name "unconnected-(U1-P3.3{slash}INT1{slash}MISO_4{slash}SDA_4{slash}PWM4N_4{slash}PWM7_2-Pad30)") (class "Default")
      (node (ref "U1") (pin "30") (pinfunction "P3.3/INT1/MISO_4/SDA_4/PWM4N_4/PWM7_2_30") (pintype "passive"))
    )
    (net (code "141") (name "unconnected-(U1-P3.4{slash}TO{slash}T1CLKO{slash}MOSI_4{slash}PWM4P_4{slash}PWM8_2{slash}CMPO-Pad31)") (class "Default")
      (node (ref "U1") (pin "31") (pinfunction "P3.4/TO/T1CLKO/MOSI_4/PWM4P_4/PWM8_2/CMPO_31") (pintype "passive"))
    )
    (net (code "142") (name "unconnected-(U1-P3.5{slash}T1{slash}TOCLKO{slash}ss_4{slash}PWMFLT-Pad34)") (class "Default")
      (node (ref "U1") (pin "34") (pinfunction "P3.5/T1/TOCLKO/ss_4/PWMFLT_34") (pintype "passive"))
    )
    (net (code "143") (name "unconnected-(U1-P3.6{slash}INT2{slash}RxD_2{slash}CMP--Pad35)") (class "Default")
      (node (ref "U1") (pin "35") (pinfunction "P3.6/INT2/RxD_2/CMP-_35") (pintype "passive"))
    )
    (net (code "144") (name "unconnected-(U1-P3.7{slash}INT3{slash}TxD_2{slash}CMP+-Pad36)") (class "Default")
      (node (ref "U1") (pin "36") (pinfunction "P3.7/INT3/TxD_2/CMP+_36") (pintype "passive"))
    )
    (net (code "145") (name "unconnected-(U1-P4.0{slash}MOSI_3{slash}S1MOS_3{slash}S2MOSl_3-Pad22)") (class "Default")
      (node (ref "U1") (pin "22") (pinfunction "P4.0/MOSI_3/S1MOS_3/S2MOSl_3_22") (pintype "passive"))
    )
    (net (code "146") (name "unconnected-(U1-P4.1{slash}MISo_3{slash}S1MISO_3{slash}S2MISO_3{slash}CMPO_2{slash}PWMETI_2-Pad41)") (class "Default")
      (node (ref "U1") (pin "41") (pinfunction "P4.1/MISo_3/S1MISO_3/S2MISO_3/CMPO_2/PWMETI_2_41") (pintype "passive"))
    )
    (net (code "147") (name "unconnected-(U1-P4.2{slash}WR{slash}CAN_RX_3-Pad42)") (class "Default")
      (node (ref "U1") (pin "42") (pinfunction "P4.2/WR/CAN_RX_3_42") (pintype "passive"))
    )
    (net (code "148") (name "unconnected-(U1-P4.3{slash}RxD_4{slash}SCLK_3{slash}S1SCLK_3{slash}S2SCLK_3-Pad43)") (class "Default")
      (node (ref "U1") (pin "43") (pinfunction "P4.3/RxD_4/SCLK_3/S1SCLK_3/S2SCLK_3_43") (pintype "passive"))
    )
    (net (code "149") (name "unconnected-(U1-P4.4{slash}RD{slash}TxD_4-Pad44)") (class "Default")
      (node (ref "U1") (pin "44") (pinfunction "P4.4/RD/TxD_4_44") (pintype "passive"))
    )
    (net (code "150") (name "unconnected-(U1-P5.0{slash}RxD3_2{slash}CMP+_2{slash}CAN_RX_2-Pad32)") (class "Default")
      (node (ref "U1") (pin "32") (pinfunction "P5.0/RxD3_2/CMP+_2/CAN_RX_2_32") (pintype "passive"))
    )
    (net (code "151") (name "unconnected-(U1-P5.1{slash}TxD3_2{slash}CMP+_3{slash}CAN_TX_2-Pad33)") (class "Default")
      (node (ref "U1") (pin "33") (pinfunction "P5.1/TxD3_2/CMP+_3/CAN_TX_2_33") (pintype "passive"))
    )
    (net (code "152") (name "unconnected-(U1-P5.4{slash}RST{slash}MCLKO{slash}SS{slash}ss_3{slash}81SS{slash}S1SS_3{slash}s2SS{slash}S2sS_3{slash}PWM2P{slash}PWM6_2IADC2IT2-Pad18)") (class "Default")
      (node (ref "U1") (pin "18") (pinfunction "P5.4/RST/MCLKO/SS/ss_3/81SS/S1SS_3/s2SS/S2sS_3/PWM2P/PWM6_2IADC2IT2_18") (pintype "passive"))
    )
    (net (code "153") (name "unconnected-(U1-P6.4{slash}PWM3P_3{slash}S1ss_4-Pad23)") (class "Default")
      (node (ref "U1") (pin "23") (pinfunction "P6.4/PWM3P_3/S1ss_4_23") (pintype "passive"))
    )
    (net (code "154") (name "unconnected-(U1-P6.5{slash}PWM3N_3{slash}S1MOSl_4-Pad24)") (class "Default")
      (node (ref "U1") (pin "24") (pinfunction "P6.5/PWM3N_3/S1MOSl_4_24") (pintype "passive"))
    )
    (net (code "155") (name "unconnected-(U1-P6.6{slash}PWM4P_3{slash}S1MISO_4-Pad25)") (class "Default")
      (node (ref "U1") (pin "25") (pinfunction "P6.6/PWM4P_3/S1MISO_4_25") (pintype "passive"))
    )
    (net (code "156") (name "unconnected-(U1-P6.7{slash}PWM4N_3{slash}S1SCLK_4-Pad26)") (class "Default")
      (node (ref "U1") (pin "26") (pinfunction "P6.7/PWM4N_3/S1SCLK_4_26") (pintype "passive"))
    )
    (net (code "157") (name "unconnected-(U1-P7.0{slash}CAN_RX_4-Pad37)") (class "Default")
      (node (ref "U1") (pin "37") (pinfunction "P7.0/CAN_RX_4_37") (pintype "passive"))
    )
    (net (code "158") (name "unconnected-(U1-P7.1{slash}CAN_TX_4-Pad38)") (class "Default")
      (node (ref "U1") (pin "38") (pinfunction "P7.1/CAN_TX_4_38") (pintype "passive"))
    )
    (net (code "159") (name "unconnected-(U1-P7.2{slash}CAN2_RX_4{slash}LIN_RX_4-Pad39)") (class "Default")
      (node (ref "U1") (pin "39") (pinfunction "P7.2/CAN2_RX_4/LIN_RX_4_39") (pintype "passive"))
    )
    (net (code "160") (name "unconnected-(U1-P7.3{slash}CAN2_TX_4{slash}LIN_TX_4{slash}PWMETI_3-Pad40)") (class "Default")
      (node (ref "U1") (pin "40") (pinfunction "P7.3/CAN2_TX_4/LIN_TX_4/PWMETI_3_40") (pintype "passive"))
    )
    (net (code "161") (name "unconnected-(U1-PWM1N_3{slash}P6.1-Pad6)") (class "Default")
      (node (ref "U1") (pin "6") (pinfunction "PWM1N_3/P6.1_6") (pintype "passive"))
    )
    (net (code "162") (name "unconnected-(U1-PWM1P_3{slash}P6.0-Pad5)") (class "Default")
      (node (ref "U1") (pin "5") (pinfunction "PWM1P_3/P6.0_5") (pintype "passive"))
    )
    (net (code "163") (name "unconnected-(U1-PWM2N_3{slash}P6.3-Pad8)") (class "Default")
      (node (ref "U1") (pin "8") (pinfunction "PWM2N_3/P6.3_8") (pintype "passive"))
    )
    (net (code "164") (name "unconnected-(U1-PWM2P_3{slash}P6.2-Pad7)") (class "Default")
      (node (ref "U1") (pin "7") (pinfunction "PWM2P_3/P6.2_7") (pintype "passive"))
    )
    (net (code "165") (name "unconnected-(U1-PWM4N_2{slash}A15{slash}P2.7-Pad52)") (class "Default")
      (node (ref "U1") (pin "52") (pinfunction "PWM4N_2/A15/P2.7_52") (pintype "passive"))
    )
    (net (code "166") (name "unconnected-(U1-PWM4P_2{slash}A14{slash}P2.6-Pad51)") (class "Default")
      (node (ref "U1") (pin "51") (pinfunction "PWM4P_2/A14/P2.6_51") (pintype "passive"))
    )
    (net (code "167") (name "unconnected-(U1-PWMETI2_2{slash}T4{slash}ADC14{slash}AD6{slash}PO.6-Pad3)") (class "Default")
      (node (ref "U1") (pin "3") (pinfunction "PWMETI2_2/T4/ADC14/AD6/PO.6_3") (pintype "passive"))
    )
    (net (code "168") (name "unconnected-(U1-RxD2{slash}PWM1PIADCO{slash}P1.0-Pad9)") (class "Default")
      (node (ref "U1") (pin "9") (pinfunction "RxD2/PWM1PIADCO/P1.0_9") (pintype "passive"))
    )
    (net (code "169") (name "unconnected-(U1-S2MISO_2{slash}S1MISO_2{slash}MISO_2{slash}SDA_2{slash}PWM3P_2{slash}A12{slash}P2.4-Pad49)") (class "Default")
      (node (ref "U1") (pin "49") (pinfunction "S2MISO_2/S1MISO_2/MISO_2/SDA_2/PWM3P_2/A12/P2.4_49") (pintype "passive"))
    )
    (net (code "170") (name "unconnected-(U1-S2MISO_4{slash}PWM7_4{slash}P7.6-Pad55)") (class "Default")
      (node (ref "U1") (pin "55") (pinfunction "S2MISO_4/PWM7_4/P7.6_55") (pintype "passive"))
    )
    (net (code "171") (name "unconnected-(U1-S2MOSl_4{slash}PWM6_4{slash}P7.5-Pad54)") (class "Default")
      (node (ref "U1") (pin "54") (pinfunction "S2MOSl_4/PWM6_4/P7.5_54") (pintype "passive"))
    )
    (net (code "172") (name "unconnected-(U1-S2SCLK_2{slash}S1SCLK_2{slash}SCLK_2{slash}SCL_2{slash}PWM3N_2{slash}A13{slash}P2.5-Pad50)") (class "Default")
      (node (ref "U1") (pin "50") (pinfunction "S2SCLK_2/S1SCLK_2/SCLK_2/SCL_2/PWM3N_2/A13/P2.5_50") (pintype "passive"))
    )
    (net (code "173") (name "unconnected-(U1-S2SCLK_4{slash}PWM8_4{slash}P7.7-Pad56)") (class "Default")
      (node (ref "U1") (pin "56") (pinfunction "S2SCLK_4/PWM8_4/P7.7_56") (pintype "passive"))
    )
    (net (code "174") (name "unconnected-(U1-S2SS_4{slash}PWM5_4{slash}P7.4-Pad53)") (class "Default")
      (node (ref "U1") (pin "53") (pinfunction "S2SS_4/PWM5_4/P7.4_53") (pintype "passive"))
    )
    (net (code "175") (name "unconnected-(U1-SDAS2MISO{slash}S1MISO{slash}MISO{slash}PWM3PIADC4{slash}P1.4-Pad12)") (class "Default")
      (node (ref "U1") (pin "12") (pinfunction "SDAS2MISO/S1MISO/MISO/PWM3PIADC4/P1.4_12") (pintype "passive"))
    )
    (net (code "176") (name "unconnected-(U1-T2CLKO{slash}S2MOSI{slash}S1MOSI{slash}MOSI{slash}PWM2N{slash}ADC3{slash}P1.3-Pad16)") (class "Default")
      (node (ref "U1") (pin "16") (pinfunction "T2CLKO/S2MOSI/S1MOSI/MOSI/PWM2N/ADC3/P1.3_16") (pintype "passive"))
    )
    (net (code "177") (name "unconnected-(U1-T3CLKO{slash}ADC13{slash}AD5{slash}P0.5-Pad2)") (class "Default")
      (node (ref "U1") (pin "2") (pinfunction "T3CLKO/ADC13/AD5/P0.5_2") (pintype "passive"))
    )
    (net (code "178") (name "unconnected-(U1-T3{slash}ADC12{slash}AD4{slash}P0.4-Pad63)") (class "Default")
      (node (ref "U1") (pin "63") (pinfunction "T3/ADC12/AD4/P0.4_63") (pintype "passive"))
    )
    (net (code "179") (name "unconnected-(U1-TxD2{slash}PWM1N{slash}ADC1{slash}P1.1-Pad10)") (class "Default")
      (node (ref "U1") (pin "10") (pinfunction "TxD2/PWM1N/ADC1/P1.1_10") (pintype "passive"))
    )
    (net (code "180") (name "unconnected-(U1-sCL{slash}s2SCLK{slash}S1SCLK{slash}SCLK{slash}PWM3N{slash}ADC5{slash}P1.5-Pad13)") (class "Default")
      (node (ref "U1") (pin "13") (pinfunction "sCL/s2SCLK/S1SCLK/SCLK/PWM3N/ADC5/P1.5_13") (pintype "passive"))
    )
    (net (code "181") (name "unconnected-(USB2-Pad0)") (class "Default")
      (node (ref "USB2") (pin "0") (pinfunction "0_0") (pintype "passive+no_connect"))
    )
    (net (code "182") (name "unconnected-(USB2-Pad0)_1") (class "Default")
      (node (ref "USB2") (pin "0") (pinfunction "0_0") (pintype "passive+no_connect"))
    )
    (net (code "183") (name "unconnected-(USB2-Pad0)_2") (class "Default")
      (node (ref "USB2") (pin "0") (pinfunction "0_0") (pintype "passive+no_connect"))
    )
    (net (code "184") (name "unconnected-(USB2-Pad0)_3") (class "Default")
      (node (ref "USB2") (pin "0") (pinfunction "0_0") (pintype "passive+no_connect"))
    )
    (net (code "185") (name "unconnected-(USB2-SBU1-PadA8)") (class "Default")
      (node (ref "USB2") (pin "A8") (pinfunction "SBU1_A8") (pintype "passive+no_connect"))
    )
    (net (code "186") (name "unconnected-(USB2-SBU2-PadB8)") (class "Default")
      (node (ref "USB2") (pin "B8") (pinfunction "SBU2_B8") (pintype "passive+no_connect"))
    )
  )
)
